# LC_Meter.net
KiCad netlist of a schematic drawn in EAGLE
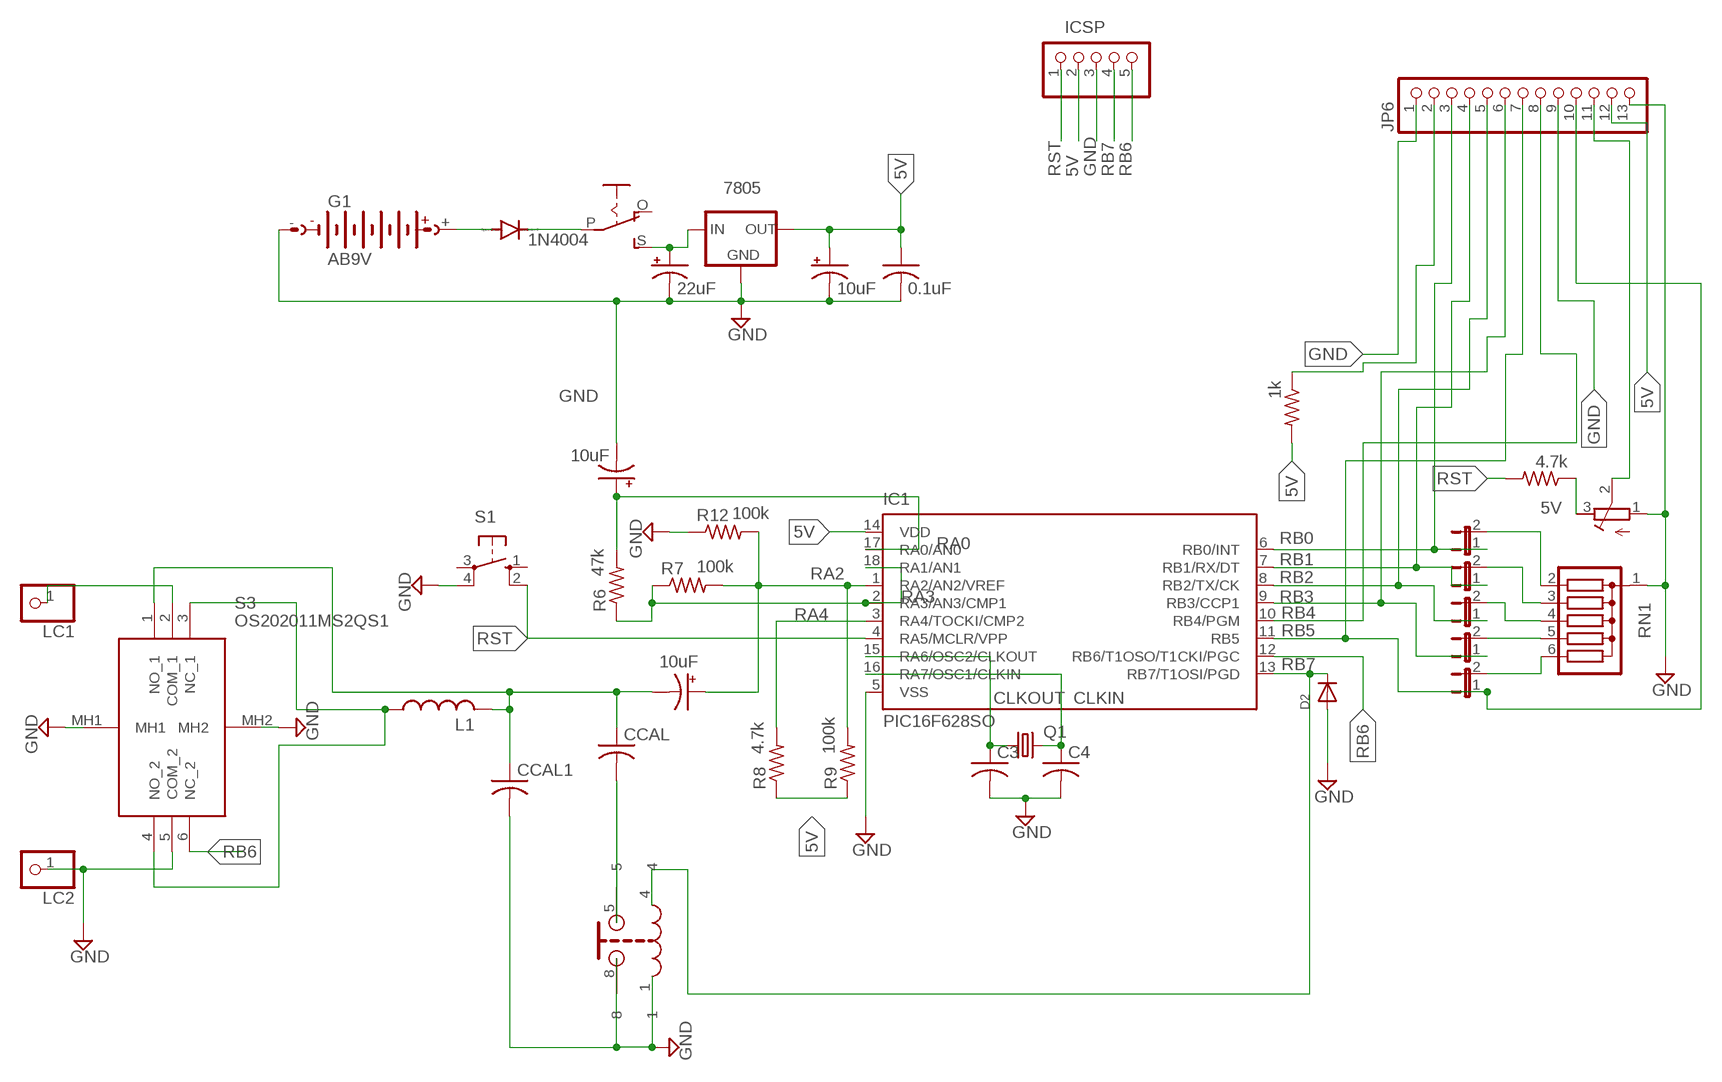
[diagram p0: schematic, sheet 1]

(export (version "E")
  (design (tool "Eeschema 10.0.6"))
  (components
    (comp (ref "C1")
      (value "22uF")
      (footprint "eagle-import:B_3528-21R")
      (libsource (lib "eagle-import") (part "CPOL-USB/3528-21R"))
    )
    (comp (ref "C2")
      (value "0.1uF")
      (footprint "eagle-import:C0603")
      (libsource (lib "eagle-import") (part "C-USC0603"))
    )
    (comp (ref "C3")
      (value "C-USC0603")
      (footprint "eagle-import:C0603")
      (libsource (lib "eagle-import") (part "C-USC0603"))
    )
    (comp (ref "C4")
      (value "C-USC0603")
      (footprint "eagle-import:C0603")
      (libsource (lib "eagle-import") (part "C-USC0603"))
    )
    (comp (ref "C5")
      (value "10uF")
      (footprint "eagle-import:E2-4")
      (libsource (lib "eagle-import") (part "rcl_334_CPOL-USE2-4"))
    )
    (comp (ref "C6")
      (value "10uF")
      (footprint "eagle-import:E2-4")
      (libsource (lib "eagle-import") (part "rcl_334_CPOL-USE2-4"))
    )
    (comp (ref "C7")
      (value "10uF")
      (footprint "eagle-import:E2-4")
      (libsource (lib "eagle-import") (part "rcl_334_CPOL-USE2-4"))
    )
    (comp (ref "CCAL")
      (value "C-US050-035X075")
      (footprint "eagle-import:C050-035X075")
      (libsource (lib "eagle-import") (part "C-US050-035X075"))
    )
    (comp (ref "CCAL1")
      (value "C-US050-035X075")
      (footprint "eagle-import:C050-035X075")
      (libsource (lib "eagle-import") (part "C-US050-035X075"))
    )
    (comp (ref "D1")
      (value "1N4004")
      (footprint "eagle-import:DO41-10")
      (libsource (lib "eagle-import") (part "1N4004"))
    )
    (comp (ref "D2")
      (value "DIODEDO-1N4148")
      (footprint "eagle-import:DO-1N4148")
      (libsource (lib "eagle-import") (part "DIODEDO-1N4148"))
    )
    (comp (ref "G1")
      (value "AB9V")
      (footprint "eagle-import:AB9V")
      (libsource (lib "eagle-import") (part "AB9V"))
    )
    (comp (ref "IC1")
      (value "PIC16F628SO")
      (footprint "eagle-import:SO-18W")
      (fields (field (name "MF") "MICROCHIP") (field (name "MPN") "PIC16F628-20I/SO"))
      (libsource (lib "eagle-import") (part "PIC16F62SO8"))
    )
    (comp (ref "ICSP")
      (value "PINHD-1X5")
      (footprint "eagle-import:1X05")
      (libsource (lib "eagle-import") (part "PINHD-1X5"))
    )
    (comp (ref "JP1")
      (value "JP1E")
      (footprint "eagle-import:JP1")
      (libsource (lib "eagle-import") (part "JP1E"))
    )
    (comp (ref "JP2")
      (value "JP1E")
      (footprint "eagle-import:JP1")
      (libsource (lib "eagle-import") (part "JP1E"))
    )
    (comp (ref "JP3")
      (value "JP1E")
      (footprint "eagle-import:JP1")
      (libsource (lib "eagle-import") (part "JP1E"))
    )
    (comp (ref "JP4")
      (value "JP1E")
      (footprint "eagle-import:JP1")
      (libsource (lib "eagle-import") (part "JP1E"))
    )
    (comp (ref "JP5")
      (value "JP1E")
      (footprint "eagle-import:JP1")
      (libsource (lib "eagle-import") (part "JP1E"))
    )
    (comp (ref "JP6")
      (value "PINHD-1X13")
      (footprint "eagle-import:1X13")
      (libsource (lib "eagle-import") (part "PINHD-1X13"))
    )
    (comp (ref "L1")
      (value "L-US0207/12")
      (footprint "eagle-import:0207_12")
      (libsource (lib "eagle-import") (part "L-US0207/12"))
    )
    (comp (ref "LC1")
      (value "PINHD-1X1")
      (footprint "eagle-import:1X01")
      (libsource (lib "eagle-import") (part "PINHD-1X1"))
    )
    (comp (ref "LC2")
      (value "PINHD-1X1")
      (footprint "eagle-import:1X01")
      (libsource (lib "eagle-import") (part "PINHD-1X1"))
    )
    (comp (ref "Q1")
      (value "CRYSTALHC49S")
      (footprint "eagle-import:HC49_S")
      (libsource (lib "eagle-import") (part "CRYSTALHC49S"))
    )
    (comp (ref "R1")
      (value "1k")
      (footprint "eagle-import:R0603")
      (libsource (lib "eagle-import") (part "R-US_R0603"))
    )
    (comp (ref "R6")
      (value "47k")
      (footprint "eagle-import:0204_7")
      (libsource (lib "eagle-import") (part "R-US_0204/7"))
    )
    (comp (ref "R7")
      (value "100k")
      (footprint "eagle-import:0204_7")
      (libsource (lib "eagle-import") (part "R-US_0204/7"))
    )
    (comp (ref "R8")
      (value "4.7k")
      (footprint "eagle-import:0204_7")
      (libsource (lib "eagle-import") (part "R-US_0204/7"))
    )
    (comp (ref "R9")
      (value "100k")
      (footprint "eagle-import:0204_7")
      (libsource (lib "eagle-import") (part "R-US_0204/7"))
    )
    (comp (ref "R10")
      (value "4.7k")
      (footprint "eagle-import:0204_7")
      (libsource (lib "eagle-import") (part "R-US_0204/7"))
    )
    (comp (ref "R11")
      (value "R-TRIMM3339P")
      (footprint "eagle-import:RTRIM3339P")
      (libsource (lib "eagle-import") (part "R-TRIMM3339P"))
    )
    (comp (ref "R12")
      (value "100k")
      (footprint "eagle-import:0204_7")
      (libsource (lib "eagle-import") (part "R-US_0204/7"))
    )
    (comp (ref "REED")
      (value "REEDRELAY")
      (footprint "eagle-import:COTO2204")
      (libsource (lib "eagle-import") (part "REEDRELAY"))
    )
    (comp (ref "RN1")
      (value "G05R")
      (footprint "eagle-import:SIL6")
      (libsource (lib "eagle-import") (part "G05R"))
    )
    (comp (ref "S1")
      (value "10-XX")
      (footprint "eagle-import:B3F-10XX")
      (fields (field (name "MPN") "B3F-1000"))
      (libsource (lib "eagle-import") (part "10-XX"))
    )
    (comp (ref "S2")
      (value "EG1218S")
      (footprint "eagle-import:EG1218")
      (libsource (lib "eagle-import") (part "EG1218S"))
    )
    (comp (ref "S3")
      (value "OS202011MS2QS1")
      (footprint "eagle-import:OS202011MS2QS1")
      (fields (field (name "MOUSER_PART_NUMBER") "611-OS202011MS2QS1"))
      (libsource (lib "eagle-import") (part "OS202011MS2QS1"))
    )
    (comp (ref "VREG")
      (value "7805")
      (footprint "eagle-import:78XXS")
      (libsource (lib "eagle-import") (part "78XXS"))
    )
  )
  (nets
    (net (code "1") (name "/CLKIN") (class "Default")
      (node (ref "C4") (pin "1") (pinfunction "1_1") (pintype "passive"))
      (node (ref "IC1") (pin "16") (pinfunction "RA7/OSC1/CLKIN_16") (pintype "bidirectional"))
      (node (ref "Q1") (pin "2") (pinfunction "2_2") (pintype "passive"))
    )
    (net (code "2") (name "/CLKOUT") (class "Default")
      (node (ref "C3") (pin "1") (pinfunction "1_1") (pintype "passive"))
      (node (ref "IC1") (pin "15") (pinfunction "RA6/OSC2/CLKOUT_15") (pintype "bidirectional"))
      (node (ref "Q1") (pin "1") (pinfunction "1_1") (pintype "passive"))
    )
    (net (code "3") (name "/RA0") (class "Default")
      (node (ref "C7") (pin "+") (pinfunction "+_+") (pintype "passive"))
      (node (ref "IC1") (pin "17") (pinfunction "RA0/AN0_17") (pintype "bidirectional"))
      (node (ref "R6") (pin "2") (pinfunction "2_2") (pintype "passive"))
    )
    (net (code "4") (name "/RA2") (class "Default")
      (node (ref "C5") (pin "+") (pinfunction "+_+") (pintype "passive"))
      (node (ref "IC1") (pin "1") (pinfunction "RA2/AN2/VREF_1") (pintype "bidirectional"))
      (node (ref "R12") (pin "2") (pinfunction "2_2") (pintype "passive"))
      (node (ref "R7") (pin "2") (pinfunction "2_2") (pintype "passive"))
      (node (ref "R9") (pin "2") (pinfunction "2_2") (pintype "passive"))
    )
    (net (code "5") (name "/RA3") (class "Default")
      (node (ref "IC1") (pin "18") (pinfunction "RA1/AN1_18") (pintype "bidirectional"))
      (node (ref "IC1") (pin "2") (pinfunction "RA3/AN3/CMP1_2") (pintype "bidirectional"))
      (node (ref "R6") (pin "1") (pinfunction "1_1") (pintype "passive"))
      (node (ref "R7") (pin "1") (pinfunction "1_1") (pintype "passive"))
    )
    (net (code "6") (name "/RA4") (class "Default")
      (node (ref "IC1") (pin "3") (pinfunction "RA4/TOCKI/CMP2_3") (pintype "bidirectional"))
      (node (ref "R8") (pin "2") (pinfunction "2_2") (pintype "passive"))
    )
    (net (code "7") (name "/RB0") (class "Default")
      (node (ref "IC1") (pin "6") (pinfunction "RB0/INT_6") (pintype "bidirectional"))
      (node (ref "JP1") (pin "1") (pinfunction "1_1") (pintype "passive"))
      (node (ref "JP6") (pin "3") (pinfunction "3_3") (pintype "passive"))
    )
    (net (code "8") (name "/RB1") (class "Default")
      (node (ref "IC1") (pin "7") (pinfunction "RB1/RX/DT_7") (pintype "bidirectional"))
      (node (ref "JP2") (pin "1") (pinfunction "1_1") (pintype "passive"))
      (node (ref "JP6") (pin "4") (pinfunction "4_4") (pintype "passive"))
    )
    (net (code "9") (name "/RB2") (class "Default")
      (node (ref "IC1") (pin "8") (pinfunction "RB2/TX/CK_8") (pintype "bidirectional"))
      (node (ref "JP3") (pin "1") (pinfunction "1_1") (pintype "passive"))
      (node (ref "JP6") (pin "5") (pinfunction "5_5") (pintype "passive"))
    )
    (net (code "10") (name "/RB3") (class "Default")
      (node (ref "IC1") (pin "9") (pinfunction "RB3/CCP1_9") (pintype "bidirectional"))
      (node (ref "JP4") (pin "1") (pinfunction "1_1") (pintype "passive"))
      (node (ref "JP6") (pin "6") (pinfunction "6_6") (pintype "passive"))
    )
    (net (code "11") (name "/RB4") (class "Default")
      (node (ref "IC1") (pin "10") (pinfunction "RB4/PGM_10") (pintype "bidirectional"))
      (node (ref "JP6") (pin "8") (pinfunction "8_8") (pintype "passive"))
    )
    (net (code "12") (name "/RB5") (class "Default")
      (node (ref "IC1") (pin "11") (pinfunction "RB5_11") (pintype "bidirectional"))
      (node (ref "JP5") (pin "1") (pinfunction "1_1") (pintype "passive"))
      (node (ref "JP6") (pin "10") (pinfunction "10_10") (pintype "passive"))
      (node (ref "JP6") (pin "7") (pinfunction "7_7") (pintype "passive"))
    )
    (net (code "13") (name "/RB7") (class "Default")
      (node (ref "D2") (pin "C") (pinfunction "C_C") (pintype "passive"))
      (node (ref "IC1") (pin "13") (pinfunction "RB7/T1OSI/PGD_13") (pintype "bidirectional"))
      (node (ref "ICSP") (pin "4") (pinfunction "4_4") (pintype "passive"))
      (node (ref "REED") (pin "4") (pinfunction "4_4") (pintype "bidirectional"))
    )
    (net (code "14") (name "5V") (class "Default")
      (node (ref "C2") (pin "1") (pinfunction "1_1") (pintype "passive"))
      (node (ref "C6") (pin "+") (pinfunction "+_+") (pintype "passive"))
      (node (ref "IC1") (pin "14") (pinfunction "VDD_14") (pintype "power_in"))
      (node (ref "ICSP") (pin "2") (pinfunction "2_2") (pintype "passive"))
      (node (ref "JP6") (pin "12") (pinfunction "12_12") (pintype "passive"))
      (node (ref "R1") (pin "2") (pinfunction "2_2") (pintype "passive"))
      (node (ref "R10") (pin "1") (pinfunction "1_1") (pintype "passive"))
      (node (ref "R11") (pin "3") (pinfunction "E_3") (pintype "passive"))
      (node (ref "R8") (pin "1") (pinfunction "1_1") (pintype "passive"))
      (node (ref "R9") (pin "1") (pinfunction "1_1") (pintype "passive"))
      (node (ref "VREG") (pin "OUT") (pinfunction "OUT_OUT") (pintype "passive"))
    )
    (net (code "15") (name "GND") (class "Default")
      (node (ref "C1") (pin "-") (pinfunction "-_-") (pintype "passive"))
      (node (ref "C2") (pin "2") (pinfunction "2_2") (pintype "passive"))
      (node (ref "C3") (pin "2") (pinfunction "2_2") (pintype "passive"))
      (node (ref "C4") (pin "2") (pinfunction "2_2") (pintype "passive"))
      (node (ref "C6") (pin "-") (pinfunction "-_-") (pintype "passive"))
      (node (ref "C7") (pin "-") (pinfunction "-_-") (pintype "passive"))
      (node (ref "CCAL1") (pin "2") (pinfunction "2_2") (pintype "passive"))
      (node (ref "D2") (pin "A") (pinfunction "A_A") (pintype "passive"))
      (node (ref "G1") (pin "-") (pinfunction "-_-") (pintype "passive"))
      (node (ref "IC1") (pin "5") (pinfunction "VSS_5") (pintype "power_in"))
      (node (ref "ICSP") (pin "3") (pinfunction "3_3") (pintype "passive"))
      (node (ref "JP6") (pin "1") (pinfunction "1_1") (pintype "passive"))
      (node (ref "JP6") (pin "13") (pinfunction "13_13") (pintype "passive"))
      (node (ref "JP6") (pin "9") (pinfunction "9_9") (pintype "passive"))
      (node (ref "LC2") (pin "1") (pinfunction "1_1") (pintype "passive"))
      (node (ref "R11") (pin "1") (pinfunction "A_1") (pintype "passive"))
      (node (ref "R12") (pin "1") (pinfunction "1_1") (pintype "passive"))
      (node (ref "REED") (pin "1") (pinfunction "1_1") (pintype "bidirectional"))
      (node (ref "REED") (pin "8") (pinfunction "8_8") (pintype "bidirectional"))
      (node (ref "RN1") (pin "1") (pinfunction "1_1") (pintype "passive"))
      (node (ref "S1") (pin "4") (pinfunction "P1_4") (pintype "passive"))
      (node (ref "S3") (pin "5") (pinfunction "COM_2_5") (pintype "bidirectional"))
      (node (ref "S3") (pin "MH1") (pinfunction "MH1_MH1") (pintype "bidirectional"))
      (node (ref "S3") (pin "MH2") (pinfunction "MH2_MH2") (pintype "bidirectional"))
      (node (ref "VREG") (pin "GND") (pinfunction "GND_GND") (pintype "input"))
    )
    (net (code "16") (name "Net-(C1-Pad+)") (class "Default")
      (node (ref "C1") (pin "+") (pinfunction "+_+") (pintype "passive"))
      (node (ref "S2") (pin "S") (pinfunction "S_S") (pintype "passive"))
      (node (ref "VREG") (pin "IN") (pinfunction "IN_IN") (pintype "input"))
    )
    (net (code "17") (name "Net-(CCAL-Pad2)") (class "Default")
      (node (ref "CCAL") (pin "2") (pinfunction "2_2") (pintype "passive"))
      (node (ref "REED") (pin "5") (pinfunction "5_5") (pintype "bidirectional"))
    )
    (net (code "18") (name "Net-(D1-PadA)") (class "Default")
      (node (ref "D1") (pin "A") (pinfunction "A_A") (pintype "passive"))
      (node (ref "G1") (pin "+") (pinfunction "+_+") (pintype "passive"))
    )
    (net (code "19") (name "Net-(D1-PadC)") (class "Default")
      (node (ref "D1") (pin "C") (pinfunction "C_C") (pintype "passive"))
      (node (ref "S2") (pin "P") (pinfunction "P_P") (pintype "passive"))
    )
    (net (code "20") (name "Net-(JP1-Pad2)") (class "Default")
      (node (ref "JP1") (pin "2") (pinfunction "2_2") (pintype "passive"))
      (node (ref "RN1") (pin "2") (pinfunction "2_2") (pintype "passive"))
    )
    (net (code "21") (name "Net-(JP2-Pad2)") (class "Default")
      (node (ref "JP2") (pin "2") (pinfunction "2_2") (pintype "passive"))
      (node (ref "RN1") (pin "3") (pinfunction "3_3") (pintype "passive"))
    )
    (net (code "22") (name "Net-(JP3-Pad2)") (class "Default")
      (node (ref "JP3") (pin "2") (pinfunction "2_2") (pintype "passive"))
      (node (ref "RN1") (pin "4") (pinfunction "4_4") (pintype "passive"))
    )
    (net (code "23") (name "Net-(JP4-Pad2)") (class "Default")
      (node (ref "JP4") (pin "2") (pinfunction "2_2") (pintype "passive"))
      (node (ref "RN1") (pin "5") (pinfunction "5_5") (pintype "passive"))
    )
    (net (code "24") (name "Net-(JP5-Pad2)") (class "Default")
      (node (ref "JP5") (pin "2") (pinfunction "2_2") (pintype "passive"))
      (node (ref "RN1") (pin "6") (pinfunction "6_6") (pintype "passive"))
    )
    (net (code "25") (name "Net-(JP6-Pad2)") (class "Default")
      (node (ref "JP6") (pin "2") (pinfunction "2_2") (pintype "passive"))
      (node (ref "R1") (pin "1") (pinfunction "1_1") (pintype "passive"))
    )
    (net (code "26") (name "Net-(R11-S)") (class "Default")
      (node (ref "JP6") (pin "11") (pinfunction "11_11") (pintype "passive"))
      (node (ref "R11") (pin "2") (pinfunction "S_2") (pintype "passive"))
    )
    (net (code "27") (name "Net-(S3-COM_1)") (class "Default")
      (node (ref "LC1") (pin "1") (pinfunction "1_1") (pintype "passive"))
      (node (ref "S3") (pin "2") (pinfunction "COM_1_2") (pintype "bidirectional"))
    )
    (net (code "28") (name "Net-(S3-NC_1)") (class "Default")
      (node (ref "L1") (pin "1") (pinfunction "1_1") (pintype "passive"))
      (node (ref "S3") (pin "3") (pinfunction "NC_1_3") (pintype "bidirectional"))
      (node (ref "S3") (pin "4") (pinfunction "NO_2_4") (pintype "bidirectional"))
    )
    (net (code "29") (name "Net-(S3-NO_1)") (class "Default")
      (node (ref "C5") (pin "-") (pinfunction "-_-") (pintype "passive"))
      (node (ref "CCAL") (pin "1") (pinfunction "1_1") (pintype "passive"))
      (node (ref "CCAL1") (pin "1") (pinfunction "1_1") (pintype "passive"))
      (node (ref "L1") (pin "2") (pinfunction "2_2") (pintype "passive"))
      (node (ref "S3") (pin "1") (pinfunction "NO_1_1") (pintype "bidirectional"))
    )
    (net (code "30") (name "RB6") (class "Default")
      (node (ref "IC1") (pin "12") (pinfunction "RB6/T1OSO/T1CKI/PGC_12") (pintype "bidirectional"))
      (node (ref "ICSP") (pin "5") (pinfunction "5_5") (pintype "passive"))
      (node (ref "S3") (pin "6") (pinfunction "NC_2_6") (pintype "bidirectional"))
    )
    (net (code "31") (name "RST") (class "Default")
      (node (ref "IC1") (pin "4") (pinfunction "RA5/MCLR/VPP_4") (pintype "bidirectional"))
      (node (ref "ICSP") (pin "1") (pinfunction "1_1") (pintype "passive"))
      (node (ref "R10") (pin "2") (pinfunction "2_2") (pintype "passive"))
      (node (ref "S1") (pin "2") (pinfunction "S1_2") (pintype "passive"))
    )
    (net (code "32") (name "unconnected-(S1-P-Pad3)") (class "Default")
      (node (ref "S1") (pin "3") (pinfunction "P_3") (pintype "passive"))
    )
    (net (code "33") (name "unconnected-(S1-S-Pad1)") (class "Default")
      (node (ref "S1") (pin "1") (pinfunction "S_1") (pintype "passive"))
    )
    (net (code "34") (name "unconnected-(S2-PadO)") (class "Default")
      (node (ref "S2") (pin "O") (pinfunction "O_O") (pintype "passive"))
    )
  )
)
